# slang-lsm6dsl-palec.net
KiCad netlist of a schematic drawn in EAGLE
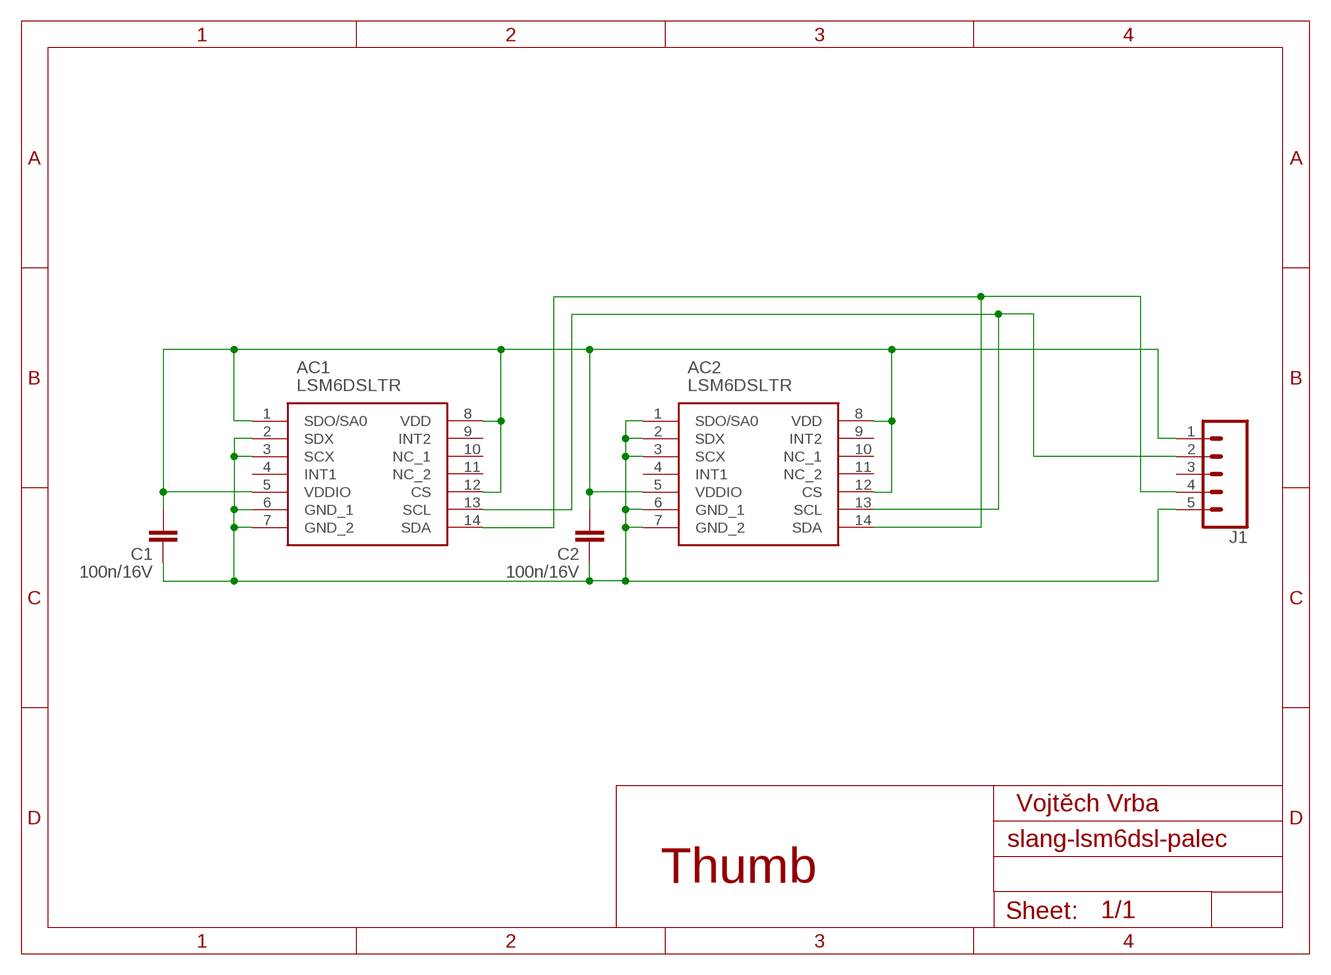
[diagram p0: schematic, sheet 1]

(export (version "E")
  (design (tool "Eeschema 10.0.6"))
  (components
    (comp (ref "AC1")
      (value "LSM6DSLTR")
      (footprint "eagle-import:LGA-14(2.5X3X0.86)")
      (fields (field (name "RS_PART_NUMBER") "1639811P"))
      (libsource (lib "eagle-import") (part "LSM6DSLTR"))
    )
    (comp (ref "AC2")
      (value "LSM6DSLTR")
      (footprint "eagle-import:LGA-14(2.5X3X0.86)")
      (fields (field (name "RS_PART_NUMBER") "1639811P"))
      (libsource (lib "eagle-import") (part "LSM6DSLTR"))
    )
    (comp (ref "C1")
      (value "100n/16V")
      (footprint "eagle-import:C0603")
      (libsource (lib "eagle-import") (part "C-EUC0603"))
    )
    (comp (ref "C2")
      (value "100n/16V")
      (footprint "eagle-import:C0603")
      (libsource (lib "eagle-import") (part "C-EUC0603"))
    )
    (comp (ref "J1")
      (value "CONN_051.27MM")
      (footprint "eagle-import:1X05_1.27MM")
      (libsource (lib "eagle-import") (part "CONN_051.27MM"))
    )
  )
  (nets
    (net (code "1") (name "Net-(AC1-CS)") (class "Default")
      (node (ref "AC1") (pin "1") (pinfunction "SDO/SA0_1") (pintype "bidirectional"))
      (node (ref "AC1") (pin "12") (pinfunction "CS_12") (pintype "bidirectional"))
      (node (ref "AC1") (pin "5") (pinfunction "VDDIO_5") (pintype "bidirectional"))
      (node (ref "AC1") (pin "8") (pinfunction "VDD_8") (pintype "bidirectional"))
      (node (ref "AC2") (pin "12") (pinfunction "CS_12") (pintype "bidirectional"))
      (node (ref "AC2") (pin "5") (pinfunction "VDDIO_5") (pintype "bidirectional"))
      (node (ref "AC2") (pin "8") (pinfunction "VDD_8") (pintype "bidirectional"))
      (node (ref "C1") (pin "2") (pinfunction "2_2") (pintype "passive"))
      (node (ref "C2") (pin "2") (pinfunction "2_2") (pintype "passive"))
      (node (ref "J1") (pin "1") (pinfunction "1_1") (pintype "passive"))
    )
    (net (code "2") (name "Net-(AC1-GND_1)") (class "Default")
      (node (ref "AC1") (pin "2") (pinfunction "SDX_2") (pintype "bidirectional"))
      (node (ref "AC1") (pin "3") (pinfunction "SCX_3") (pintype "bidirectional"))
      (node (ref "AC1") (pin "6") (pinfunction "GND_1_6") (pintype "bidirectional"))
      (node (ref "AC1") (pin "7") (pinfunction "GND_2_7") (pintype "bidirectional"))
      (node (ref "AC2") (pin "1") (pinfunction "SDO/SA0_1") (pintype "bidirectional"))
      (node (ref "AC2") (pin "2") (pinfunction "SDX_2") (pintype "bidirectional"))
      (node (ref "AC2") (pin "3") (pinfunction "SCX_3") (pintype "bidirectional"))
      (node (ref "AC2") (pin "6") (pinfunction "GND_1_6") (pintype "bidirectional"))
      (node (ref "AC2") (pin "7") (pinfunction "GND_2_7") (pintype "bidirectional"))
      (node (ref "C1") (pin "1") (pinfunction "1_1") (pintype "passive"))
      (node (ref "C2") (pin "1") (pinfunction "1_1") (pintype "passive"))
      (node (ref "J1") (pin "5") (pinfunction "5_5") (pintype "passive"))
    )
    (net (code "3") (name "Net-(AC1-SCL)") (class "Default")
      (node (ref "AC1") (pin "13") (pinfunction "SCL_13") (pintype "bidirectional"))
      (node (ref "AC2") (pin "13") (pinfunction "SCL_13") (pintype "bidirectional"))
      (node (ref "J1") (pin "2") (pinfunction "2_2") (pintype "passive"))
    )
    (net (code "4") (name "Net-(AC1-SDA)") (class "Default")
      (node (ref "AC1") (pin "14") (pinfunction "SDA_14") (pintype "bidirectional"))
      (node (ref "AC2") (pin "14") (pinfunction "SDA_14") (pintype "bidirectional"))
      (node (ref "J1") (pin "4") (pinfunction "4_4") (pintype "passive"))
    )
    (net (code "5") (name "unconnected-(AC1-INT1-Pad4)") (class "Default")
      (node (ref "AC1") (pin "4") (pinfunction "INT1_4") (pintype "bidirectional"))
    )
    (net (code "6") (name "unconnected-(AC1-INT2-Pad9)") (class "Default")
      (node (ref "AC1") (pin "9") (pinfunction "INT2_9") (pintype "bidirectional"))
    )
    (net (code "7") (name "unconnected-(AC1-NC_1-Pad10)") (class "Default")
      (node (ref "AC1") (pin "10") (pinfunction "NC_1_10") (pintype "bidirectional"))
    )
    (net (code "8") (name "unconnected-(AC1-NC_2-Pad11)") (class "Default")
      (node (ref "AC1") (pin "11") (pinfunction "NC_2_11") (pintype "bidirectional"))
    )
    (net (code "9") (name "unconnected-(AC2-INT1-Pad4)") (class "Default")
      (node (ref "AC2") (pin "4") (pinfunction "INT1_4") (pintype "bidirectional"))
    )
    (net (code "10") (name "unconnected-(AC2-INT2-Pad9)") (class "Default")
      (node (ref "AC2") (pin "9") (pinfunction "INT2_9") (pintype "bidirectional"))
    )
    (net (code "11") (name "unconnected-(AC2-NC_1-Pad10)") (class "Default")
      (node (ref "AC2") (pin "10") (pinfunction "NC_1_10") (pintype "bidirectional"))
    )
    (net (code "12") (name "unconnected-(AC2-NC_2-Pad11)") (class "Default")
      (node (ref "AC2") (pin "11") (pinfunction "NC_2_11") (pintype "bidirectional"))
    )
    (net (code "13") (name "unconnected-(J1-Pad3)") (class "Default")
      (node (ref "J1") (pin "3") (pinfunction "3_3") (pintype "passive"))
    )
  )
)
